# z0-probe_v2.net
KiCad netlist of a schematic drawn in EAGLE
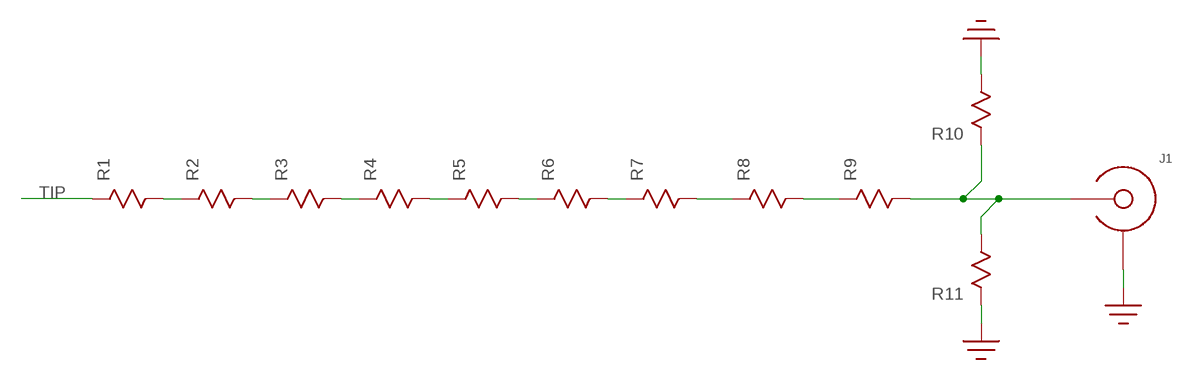
[diagram p0: schematic, sheet 1]

(export (version "E")
  (design (tool "Eeschema 10.0.6"))
  (components
    (comp (ref "J1")
      (value "SMA-EDGE-LAUNCH")
      (footprint "eagle-import:SMA_EDGE_LAUNCH_2L_4020_TAPER_FIXED")
      (libsource (lib "eagle-import") (part "SMA-EDGE-LAUNCH"))
    )
    (comp (ref "R1")
      (value "R0603")
      (footprint "eagle-import:R0603")
      (libsource (lib "eagle-import") (part "R0603"))
    )
    (comp (ref "R2")
      (value "R0603")
      (footprint "eagle-import:R0603")
      (libsource (lib "eagle-import") (part "R0603"))
    )
    (comp (ref "R3")
      (value "R0603")
      (footprint "eagle-import:R0603")
      (libsource (lib "eagle-import") (part "R0603"))
    )
    (comp (ref "R4")
      (value "R0603")
      (footprint "eagle-import:R0603")
      (libsource (lib "eagle-import") (part "R0603"))
    )
    (comp (ref "R5")
      (value "R0603")
      (footprint "eagle-import:R0603")
      (libsource (lib "eagle-import") (part "R0603"))
    )
    (comp (ref "R6")
      (value "R0603")
      (footprint "eagle-import:R0603")
      (libsource (lib "eagle-import") (part "R0603"))
    )
    (comp (ref "R7")
      (value "R0603")
      (footprint "eagle-import:R0603")
      (libsource (lib "eagle-import") (part "R0603"))
    )
    (comp (ref "R8")
      (value "R0603")
      (footprint "eagle-import:R0603")
      (libsource (lib "eagle-import") (part "R0603"))
    )
    (comp (ref "R9")
      (value "R0603")
      (footprint "eagle-import:R0603")
      (libsource (lib "eagle-import") (part "R0603"))
    )
    (comp (ref "R10")
      (value "R0603")
      (footprint "eagle-import:R0603")
      (libsource (lib "eagle-import") (part "R0603"))
    )
    (comp (ref "R11")
      (value "R0603")
      (footprint "eagle-import:R0603")
      (libsource (lib "eagle-import") (part "R0603"))
    )
  )
  (nets
    (net (code "1") (name "/TIP") (class "Default")
      (node (ref "R1") (pin "P$1") (pinfunction "P$3_P$1") (pintype "bidirectional"))
    )
    (net (code "2") (name "GND") (class "Default")
      (node (ref "J1") (pin "BOTTOM_GND") (pinfunction "SHIELD_BOTTOM_GND") (pintype "bidirectional"))
      (node (ref "J1") (pin "GND@1") (pinfunction "SHIELD_GND@1") (pintype "bidirectional"))
      (node (ref "J1") (pin "GND@14") (pinfunction "SHIELD_GND@14") (pintype "bidirectional"))
      (node (ref "J1") (pin "GND@15") (pinfunction "SHIELD_GND@15") (pintype "bidirectional"))
      (node (ref "J1") (pin "GND@16") (pinfunction "SHIELD_GND@16") (pintype "bidirectional"))
      (node (ref "J1") (pin "GND@17") (pinfunction "SHIELD_GND@17") (pintype "bidirectional"))
      (node (ref "J1") (pin "GND@2") (pinfunction "SHIELD_GND@2") (pintype "bidirectional"))
      (node (ref "J1") (pin "GND@3") (pinfunction "SHIELD_GND@3") (pintype "bidirectional"))
      (node (ref "J1") (pin "GND@4") (pinfunction "SHIELD_GND@4") (pintype "bidirectional"))
      (node (ref "J1") (pin "GND@5") (pinfunction "SHIELD_GND@5") (pintype "bidirectional"))
      (node (ref "J1") (pin "GND@6") (pinfunction "SHIELD_GND@6") (pintype "bidirectional"))
      (node (ref "J1") (pin "GND@7") (pinfunction "SHIELD_GND@7") (pintype "bidirectional"))
      (node (ref "J1") (pin "GND@8") (pinfunction "SHIELD_GND@8") (pintype "bidirectional"))
      (node (ref "J1") (pin "GND_PAD1") (pinfunction "SHIELD_GND_PAD1") (pintype "bidirectional"))
      (node (ref "J1") (pin "GND_PAD2") (pinfunction "SHIELD_GND_PAD2") (pintype "bidirectional"))
      (node (ref "J1") (pin "P$1") (pinfunction "SHIELD_P$1") (pintype "bidirectional"))
      (node (ref "J1") (pin "P$2") (pinfunction "SHIELD_P$2") (pintype "bidirectional"))
      (node (ref "R10") (pin "P$2") (pinfunction "P$4_P$2") (pintype "bidirectional"))
      (node (ref "R11") (pin "P$1") (pinfunction "P$3_P$1") (pintype "bidirectional"))
    )
    (net (code "3") (name "Net-(R1-P$4)") (class "Default")
      (node (ref "R1") (pin "P$2") (pinfunction "P$4_P$2") (pintype "bidirectional"))
      (node (ref "R2") (pin "P$1") (pinfunction "P$3_P$1") (pintype "bidirectional"))
    )
    (net (code "4") (name "Net-(R2-P$4)") (class "Default")
      (node (ref "R2") (pin "P$2") (pinfunction "P$4_P$2") (pintype "bidirectional"))
      (node (ref "R3") (pin "P$1") (pinfunction "P$3_P$1") (pintype "bidirectional"))
    )
    (net (code "5") (name "Net-(R3-P$4)") (class "Default")
      (node (ref "R3") (pin "P$2") (pinfunction "P$4_P$2") (pintype "bidirectional"))
      (node (ref "R4") (pin "P$1") (pinfunction "P$3_P$1") (pintype "bidirectional"))
    )
    (net (code "6") (name "Net-(R4-P$4)") (class "Default")
      (node (ref "R4") (pin "P$2") (pinfunction "P$4_P$2") (pintype "bidirectional"))
      (node (ref "R5") (pin "P$1") (pinfunction "P$3_P$1") (pintype "bidirectional"))
    )
    (net (code "7") (name "Net-(R5-P$4)") (class "Default")
      (node (ref "R5") (pin "P$2") (pinfunction "P$4_P$2") (pintype "bidirectional"))
      (node (ref "R6") (pin "P$1") (pinfunction "P$3_P$1") (pintype "bidirectional"))
    )
    (net (code "8") (name "Net-(R6-P$4)") (class "Default")
      (node (ref "R6") (pin "P$2") (pinfunction "P$4_P$2") (pintype "bidirectional"))
      (node (ref "R7") (pin "P$1") (pinfunction "P$3_P$1") (pintype "bidirectional"))
    )
    (net (code "9") (name "Net-(R7-P$4)") (class "Default")
      (node (ref "R7") (pin "P$2") (pinfunction "P$4_P$2") (pintype "bidirectional"))
      (node (ref "R8") (pin "P$1") (pinfunction "P$3_P$1") (pintype "bidirectional"))
    )
    (net (code "10") (name "Net-(R8-P$4)") (class "Default")
      (node (ref "R8") (pin "P$2") (pinfunction "P$4_P$2") (pintype "bidirectional"))
      (node (ref "R9") (pin "P$1") (pinfunction "P$3_P$1") (pintype "bidirectional"))
    )
    (net (code "11") (name "Net-(R10-P$3)") (class "Default")
      (node (ref "J1") (pin "CENTER@1") (pinfunction "CENTER_CENTER@1") (pintype "bidirectional"))
      (node (ref "J1") (pin "P$3") (pinfunction "CENTER_P$3") (pintype "bidirectional"))
      (node (ref "R10") (pin "P$1") (pinfunction "P$3_P$1") (pintype "bidirectional"))
      (node (ref "R11") (pin "P$2") (pinfunction "P$4_P$2") (pintype "bidirectional"))
      (node (ref "R9") (pin "P$2") (pinfunction "P$4_P$2") (pintype "bidirectional"))
    )
  )
)
